# sensor_board_v0_56.net
KiCad netlist of a schematic drawn in EAGLE
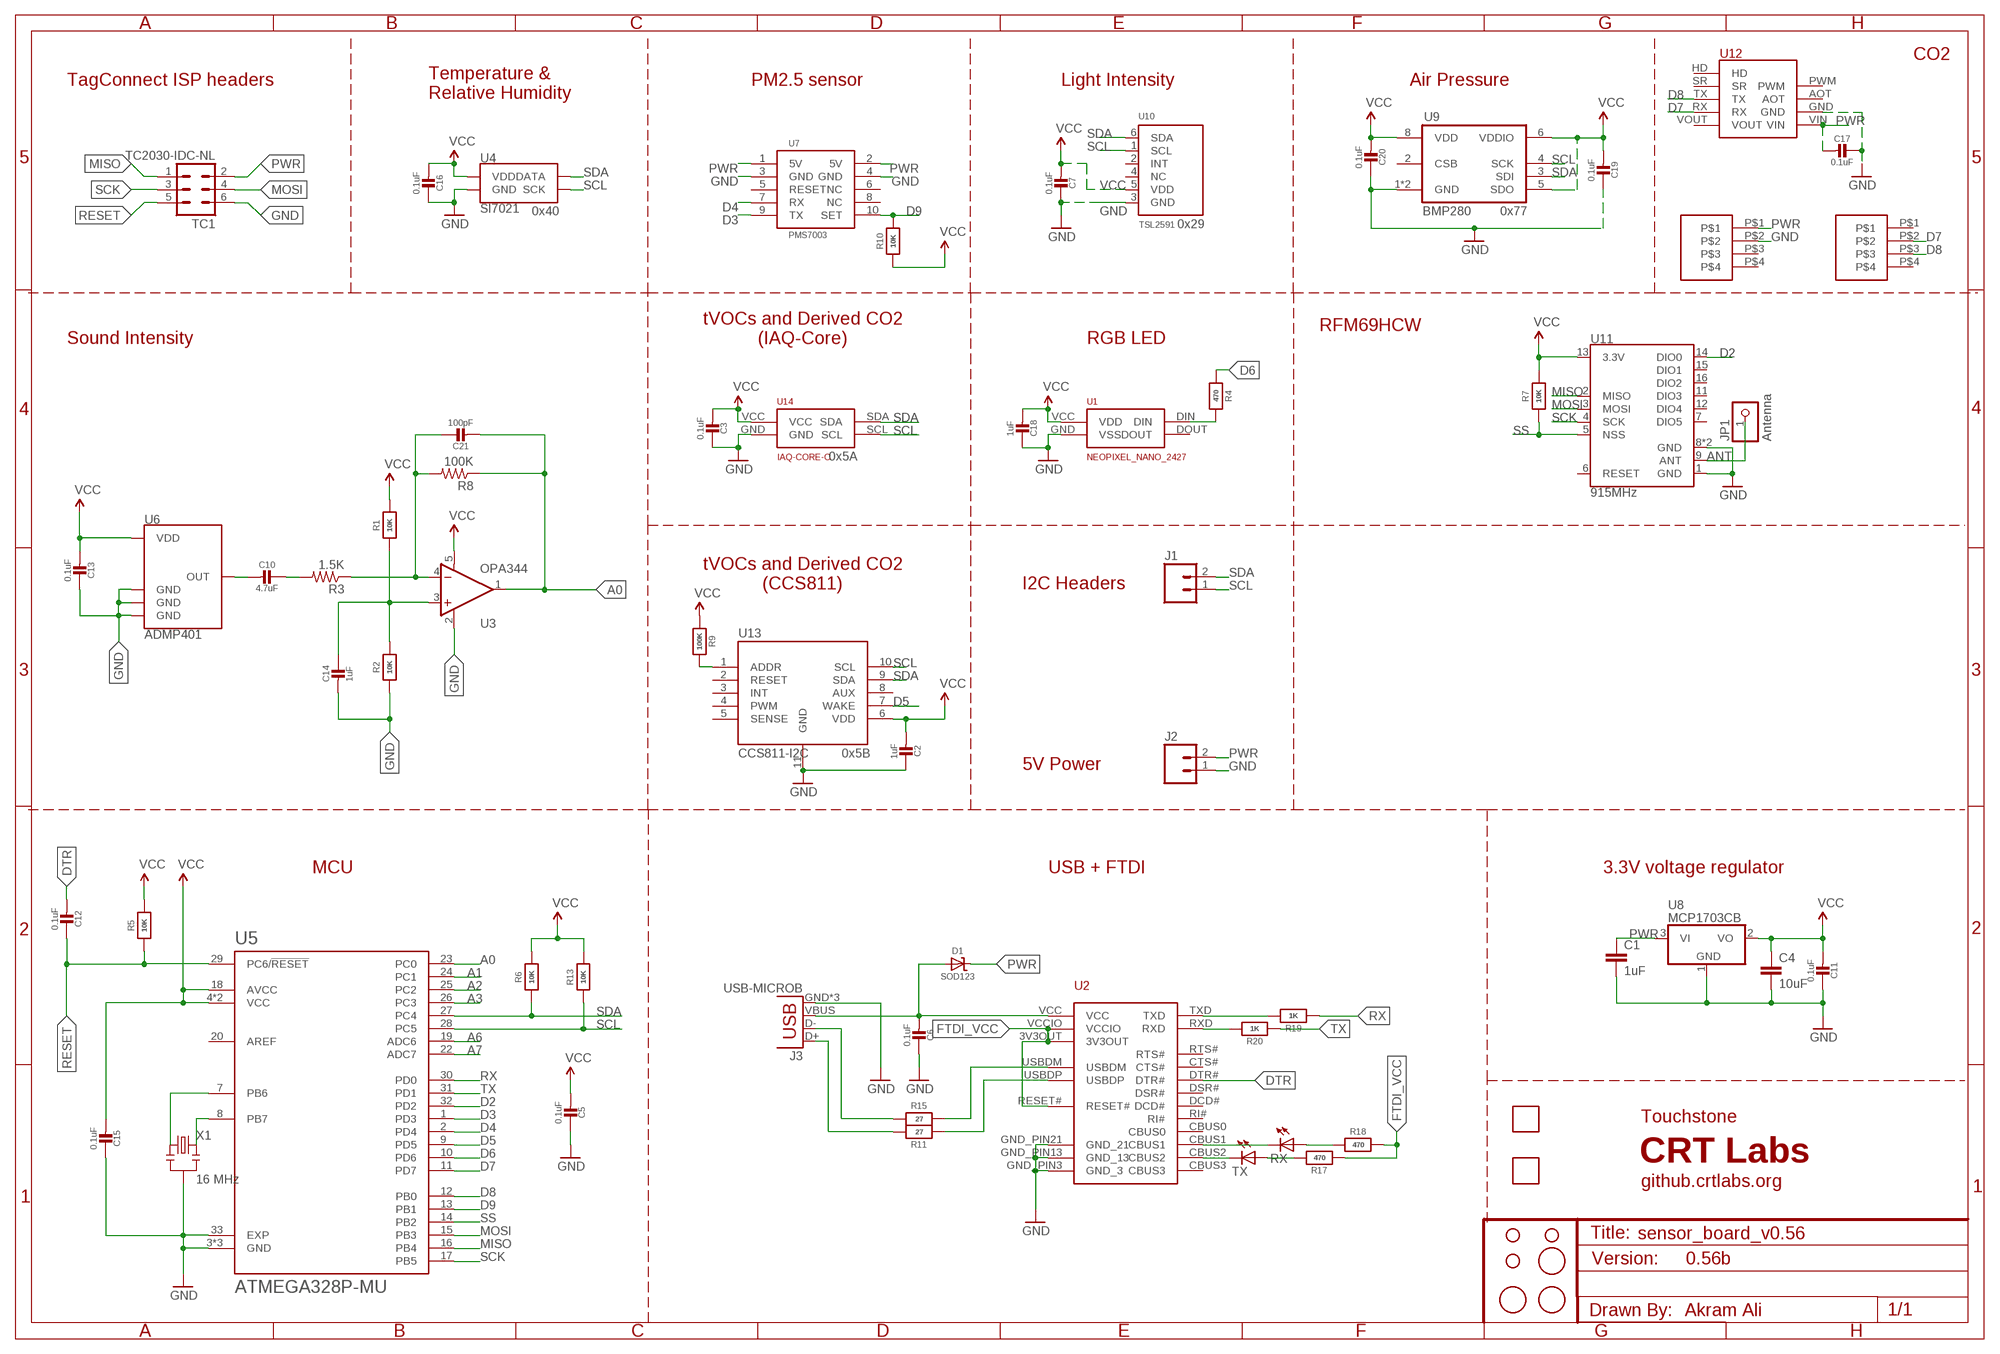
[diagram p0: schematic, sheet 1]

(export (version "E")
  (design (tool "Eeschema 10.0.6"))
  (components
    (comp (ref "C1")
      (value "1uF")
      (footprint "eagle-import:0805")
      (fields (field (name "MPN") "CC0805ZRY5V8BB105"))
      (libsource (lib "eagle-import") (part "CAP0805"))
    )
    (comp (ref "C2")
      (value "1uF")
      (footprint "eagle-import:MICROBUILDER__0402MP")
      (libsource (lib "eagle-import") (part "MICROBUILDER_CAP_CERAMIC_0402MP"))
    )
    (comp (ref "C3")
      (value "0.1uF")
      (footprint "eagle-import:MICROBUILDER__0402MP")
      (libsource (lib "eagle-import") (part "MICROBUILDER_CAP_CERAMIC_0402MP"))
    )
    (comp (ref "C4")
      (value "10uF")
      (footprint "eagle-import:0805")
      (fields (field (name "MPN") "CC0805KKX5R6BB106"))
      (libsource (lib "eagle-import") (part "CAP0805"))
    )
    (comp (ref "C5")
      (value "0.1uF")
      (footprint "eagle-import:MICROBUILDER__0402MP")
      (libsource (lib "eagle-import") (part "MICROBUILDER_CAP_CERAMIC_0402MP"))
    )
    (comp (ref "C6")
      (value "0.1uF")
      (footprint "eagle-import:MICROBUILDER__0402MP")
      (libsource (lib "eagle-import") (part "MICROBUILDER_CAP_CERAMIC_0402MP"))
    )
    (comp (ref "C7")
      (value "0.1uF")
      (footprint "eagle-import:MICROBUILDER__0402MP")
      (libsource (lib "eagle-import") (part "MICROBUILDER_CAP_CERAMIC_0402MP"))
    )
    (comp (ref "C10")
      (value "4.7uF")
      (footprint "eagle-import:MICROBUILDER__0402MP")
      (libsource (lib "eagle-import") (part "MICROBUILDER_CAP_CERAMIC_0402MP"))
    )
    (comp (ref "C11")
      (value "0.1uF")
      (footprint "eagle-import:MICROBUILDER__0402MP")
      (libsource (lib "eagle-import") (part "MICROBUILDER_CAP_CERAMIC_0402MP"))
    )
    (comp (ref "C12")
      (value "0.1uF")
      (footprint "eagle-import:MICROBUILDER__0402MP")
      (libsource (lib "eagle-import") (part "MICROBUILDER_CAP_CERAMIC_0402MP"))
    )
    (comp (ref "C13")
      (value "0.1uF")
      (footprint "eagle-import:MICROBUILDER__0402MP")
      (libsource (lib "eagle-import") (part "MICROBUILDER_CAP_CERAMIC_0402MP"))
    )
    (comp (ref "C14")
      (value "1uF")
      (footprint "eagle-import:MICROBUILDER__0402MP")
      (libsource (lib "eagle-import") (part "MICROBUILDER_CAP_CERAMIC_0402MP"))
    )
    (comp (ref "C15")
      (value "0.1uF")
      (footprint "eagle-import:MICROBUILDER__0402MP")
      (libsource (lib "eagle-import") (part "MICROBUILDER_CAP_CERAMIC_0402MP"))
    )
    (comp (ref "C16")
      (value "0.1uF")
      (footprint "eagle-import:MICROBUILDER__0402MP")
      (libsource (lib "eagle-import") (part "MICROBUILDER_CAP_CERAMIC_0402MP"))
    )
    (comp (ref "C17")
      (value "0.1uF")
      (footprint "eagle-import:MICROBUILDER__0402MP")
      (libsource (lib "eagle-import") (part "MICROBUILDER_CAP_CERAMIC_0402MP"))
    )
    (comp (ref "C18")
      (value "1uF")
      (footprint "eagle-import:MICROBUILDER__0402MP")
      (libsource (lib "eagle-import") (part "MICROBUILDER_CAP_CERAMIC_0402MP"))
    )
    (comp (ref "C19")
      (value "0.1uF")
      (footprint "eagle-import:MICROBUILDER__0402MP")
      (libsource (lib "eagle-import") (part "MICROBUILDER_CAP_CERAMIC_0402MP"))
    )
    (comp (ref "C20")
      (value "0.1uF")
      (footprint "eagle-import:MICROBUILDER__0402MP")
      (libsource (lib "eagle-import") (part "MICROBUILDER_CAP_CERAMIC_0402MP"))
    )
    (comp (ref "C21")
      (value "100pF")
      (footprint "eagle-import:MICROBUILDER__0402MP")
      (libsource (lib "eagle-import") (part "MICROBUILDER_CAP_CERAMIC_0402MP"))
    )
    (comp (ref "D1")
      (value "SOD123")
      (footprint "eagle-import:MICROBUILDER_SOD-123")
      (libsource (lib "eagle-import") (part "MICROBUILDER_DIODE-SCHOTTKYSOD-123"))
    )
    (comp (ref "H1")
      (value "STAND-OFF")
      (footprint "eagle-import:STAND-OFF")
      (libsource (lib "eagle-import") (part "STAND-OFF"))
    )
    (comp (ref "H2")
      (value "STAND-OFF")
      (footprint "eagle-import:STAND-OFF")
      (libsource (lib "eagle-import") (part "STAND-OFF"))
    )
    (comp (ref "H3")
      (value "STAND-OFF")
      (footprint "eagle-import:STAND-OFF")
      (libsource (lib "eagle-import") (part "STAND-OFF"))
    )
    (comp (ref "J1")
      (value "M02PTH")
      (footprint "eagle-import:1X02")
      (libsource (lib "eagle-import") (part "M02PTH"))
    )
    (comp (ref "J2")
      (value "M02PTH")
      (footprint "eagle-import:1X02")
      (libsource (lib "eagle-import") (part "M02PTH"))
    )
    (comp (ref "J3")
      (value "USB-MICROB")
      (footprint "eagle-import:USB-MICROB")
      (fields (field (name "MPN") "47346-0001"))
      (libsource (lib "eagle-import") (part "USB-MICROB"))
    )
    (comp (ref "JP1")
      (value "Antenna")
      (footprint "eagle-import:1X01-CLEANBIG")
      (libsource (lib "eagle-import") (part "PINHD-1X1CB"))
    )
    (comp (ref "R1")
      (value "10K")
      (footprint "eagle-import:MICROBUILDER__0402MP")
      (libsource (lib "eagle-import") (part "MICROBUILDER_RESISTOR_0402MP"))
    )
    (comp (ref "R2")
      (value "10K")
      (footprint "eagle-import:MICROBUILDER__0402MP")
      (libsource (lib "eagle-import") (part "MICROBUILDER_RESISTOR_0402MP"))
    )
    (comp (ref "R3")
      (value "1.5K")
      (footprint "eagle-import:0805")
      (fields (field (name "MPN") "RC0805FR-071K5L "))
      (libsource (lib "eagle-import") (part "RESISTOR0805-RES"))
    )
    (comp (ref "R4")
      (value "470")
      (footprint "eagle-import:MICROBUILDER__0402MP")
      (libsource (lib "eagle-import") (part "MICROBUILDER_RESISTOR_0402MP"))
    )
    (comp (ref "R5")
      (value "10K")
      (footprint "eagle-import:MICROBUILDER__0402MP")
      (libsource (lib "eagle-import") (part "MICROBUILDER_RESISTOR_0402MP"))
    )
    (comp (ref "R6")
      (value "10K")
      (footprint "eagle-import:MICROBUILDER__0402MP")
      (libsource (lib "eagle-import") (part "MICROBUILDER_RESISTOR_0402MP"))
    )
    (comp (ref "R7")
      (value "10K")
      (footprint "eagle-import:MICROBUILDER__0402MP")
      (libsource (lib "eagle-import") (part "MICROBUILDER_RESISTOR_0402MP"))
    )
    (comp (ref "R8")
      (value "100K")
      (footprint "eagle-import:0805")
      (fields (field (name "MPN") "RC0805FR-07100KL "))
      (libsource (lib "eagle-import") (part "RESISTOR0805-RES"))
    )
    (comp (ref "R9")
      (value "100K")
      (footprint "eagle-import:MICROBUILDER__0402MP")
      (libsource (lib "eagle-import") (part "MICROBUILDER_RESISTOR_0402MP"))
    )
    (comp (ref "R10")
      (value "10K")
      (footprint "eagle-import:MICROBUILDER__0402MP")
      (libsource (lib "eagle-import") (part "MICROBUILDER_RESISTOR_0402MP"))
    )
    (comp (ref "R11")
      (value "27")
      (footprint "eagle-import:MICROBUILDER__0402MP")
      (libsource (lib "eagle-import") (part "MICROBUILDER_RESISTOR_0402MP"))
    )
    (comp (ref "R13")
      (value "10K")
      (footprint "eagle-import:MICROBUILDER__0402MP")
      (libsource (lib "eagle-import") (part "MICROBUILDER_RESISTOR_0402MP"))
    )
    (comp (ref "R15")
      (value "27")
      (footprint "eagle-import:MICROBUILDER__0402MP")
      (libsource (lib "eagle-import") (part "MICROBUILDER_RESISTOR_0402MP"))
    )
    (comp (ref "R17")
      (value "470")
      (footprint "eagle-import:MICROBUILDER__0402MP")
      (libsource (lib "eagle-import") (part "MICROBUILDER_RESISTOR_0402MP"))
    )
    (comp (ref "R18")
      (value "470")
      (footprint "eagle-import:MICROBUILDER__0402MP")
      (libsource (lib "eagle-import") (part "MICROBUILDER_RESISTOR_0402MP"))
    )
    (comp (ref "R19")
      (value "1K")
      (footprint "eagle-import:MICROBUILDER__0402MP")
      (libsource (lib "eagle-import") (part "MICROBUILDER_RESISTOR_0402MP"))
    )
    (comp (ref "R20")
      (value "1K")
      (footprint "eagle-import:MICROBUILDER__0402MP")
      (libsource (lib "eagle-import") (part "MICROBUILDER_RESISTOR_0402MP"))
    )
    (comp (ref "RX")
      (value "LEDCHIPLED_0805")
      (footprint "eagle-import:CHIPLED_0805")
      (fields (field (name "MPN") "LG R971-KN-1"))
      (libsource (lib "eagle-import") (part "LEDCHIPLED_0805"))
    )
    (comp (ref "TC1")
      (value "TC2030-IDC-NL")
      (footprint "eagle-import:TC2030-IDC-NL")
      (libsource (lib "eagle-import") (part "TC2030-IDC-NL"))
    )
    (comp (ref "TX")
      (value "LEDCHIPLED_0805")
      (footprint "eagle-import:CHIPLED_0805")
      (fields (field (name "MPN") "LG R971-KN-1"))
      (libsource (lib "eagle-import") (part "LEDCHIPLED_0805"))
    )
    (comp (ref "U$1")
      (value "FIDUCIAL")
      (footprint "eagle-import:FIDUCIAL_1MM")
      (libsource (lib "eagle-import") (part "FIDUCIAL"))
    )
    (comp (ref "U$2")
      (value "FIDUCIAL")
      (footprint "eagle-import:FIDUCIAL_1MM")
      (libsource (lib "eagle-import") (part "FIDUCIAL"))
    )
    (comp (ref "U$3")
      (value "FIDUCIAL")
      (footprint "eagle-import:FIDUCIAL_1MM")
      (libsource (lib "eagle-import") (part "FIDUCIAL"))
    )
    (comp (ref "U$4")
      (value "0878980426")
      (footprint "eagle-import:CONN_4POS_VERT_2.54_SMD")
      (libsource (lib "eagle-import") (part "0878980426"))
    )
    (comp (ref "U$5")
      (value "0878980426")
      (footprint "eagle-import:CONN_4POS_VERT_2.54_SMD")
      (libsource (lib "eagle-import") (part "0878980426"))
    )
    (comp (ref "U1")
      (value "NEOPIXEL_NANO_2427")
      (footprint "eagle-import:SK6805-2427")
      (libsource (lib "eagle-import") (part "NEOPIXEL_NANO_2427"))
    )
    (comp (ref "U2")
      (value "FT231XQ-R")
      (footprint "eagle-import:FTDI_FT231XQ-R_PACKAGE")
      (libsource (lib "eagle-import") (part "FT231XQ-R"))
    )
    (comp (ref "U3")
      (value "OPA344")
      (footprint "eagle-import:SOT23-5")
      (fields (field (name "MPN") "OPA344NA/3K"))
      (libsource (lib "eagle-import") (part "OPA344"))
    )
    (comp (ref "U4")
      (value "SI7021")
      (footprint "eagle-import:DFN-6-3X3-SI7021")
      (libsource (lib "eagle-import") (part "SI7021"))
    )
    (comp (ref "U5")
      (value "ATMEGA328P-MU")
      (footprint "eagle-import:QFN50P500X500X100-33N")
      (fields (field (name "MF") "Atmel"))
      (libsource (lib "eagle-import") (part "ATMEGA328P-MU"))
    )
    (comp (ref "U6")
      (value "ADMP401")
      (footprint "eagle-import:ADMP401")
      (fields (field (name "MPN") "INMP401ACEZ-R7"))
      (libsource (lib "eagle-import") (part "ADMP401"))
    )
    (comp (ref "U7")
      (value "PMS7003")
      (footprint "eagle-import:PMS7003_RECEPTACLE_1.27MM_2X5")
      (libsource (lib "eagle-import") (part "PMS7003"))
    )
    (comp (ref "U8")
      (value "MCP1703CB")
      (footprint "eagle-import:SOT23")
      (fields (field (name "MPN") "MCP1703T-2502E/CB"))
      (libsource (lib "eagle-import") (part "MCP1703CB"))
    )
    (comp (ref "U9")
      (value "BMP280")
      (footprint "eagle-import:BMP280")
      (libsource (lib "eagle-import") (part "BMP280"))
    )
    (comp (ref "U10")
      (value "TSL2591")
      (footprint "eagle-import:DFN6_TAOS")
      (fields (field (name "MPN") "TSL25911FN "))
      (libsource (lib "eagle-import") (part "LIGHT_TSL2591"))
    )
    (comp (ref "U11")
      (value "915MHz")
      (footprint "eagle-import:RFM69HCW-XXXS2")
      (libsource (lib "eagle-import") (part "RFM69HCW-915"))
    )
    (comp (ref "U12")
      (value "MH-Z19")
      (footprint "eagle-import:MH-Z19")
      (fields (field (name "MPN") "MH-z19"))
      (libsource (lib "eagle-import") (part "MH-Z19"))
    )
    (comp (ref "U13")
      (value "CCS811-I2C")
      (footprint "eagle-import:LGA")
      (libsource (lib "eagle-import") (part "CCS811-I2C"))
    )
    (comp (ref "U14")
      (value "IAQ-CORE-C")
      (footprint "eagle-import:IAQ-CORE-C")
      (libsource (lib "eagle-import") (part "IAQ-CORE-C"))
    )
    (comp (ref "U15")
      (value "VLP-450-F")
      (footprint "eagle-import:VLP-450-F")
      (libsource (lib "eagle-import") (part "VLP-450-F"))
    )
    (comp (ref "U16")
      (value "VLP-450-F")
      (footprint "eagle-import:VLP-450-F")
      (libsource (lib "eagle-import") (part "VLP-450-F"))
    )
    (comp (ref "X1")
      (value "16 MHz")
      (footprint "eagle-import:RESONATOR-SMD")
      (libsource (lib "eagle-import") (part "RESONATORSMD"))
    )
  )
  (nets
    (net (code "1") (name "/A1") (class "Default")
      (node (ref "U5") (pin "24") (pinfunction "PC1_24") (pintype "bidirectional"))
    )
    (net (code "2") (name "/A2") (class "Default")
      (node (ref "U5") (pin "25") (pinfunction "PC2_25") (pintype "bidirectional"))
    )
    (net (code "3") (name "/A3") (class "Default")
      (node (ref "U5") (pin "26") (pinfunction "PC3_26") (pintype "bidirectional"))
    )
    (net (code "4") (name "/A6") (class "Default")
      (node (ref "U5") (pin "19") (pinfunction "ADC6_19") (pintype "bidirectional"))
    )
    (net (code "5") (name "/A7") (class "Default")
      (node (ref "U5") (pin "22") (pinfunction "ADC7_22") (pintype "bidirectional"))
    )
    (net (code "6") (name "/ANT") (class "Default")
      (node (ref "JP1") (pin "1") (pinfunction "1_1") (pintype "passive"))
      (node (ref "U11") (pin "9") (pinfunction "ANT_9") (pintype "passive"))
    )
    (net (code "7") (name "/D2") (class "Default")
      (node (ref "U11") (pin "14") (pinfunction "DIO0_14") (pintype "bidirectional"))
      (node (ref "U5") (pin "32") (pinfunction "PD2_32") (pintype "bidirectional"))
    )
    (net (code "8") (name "/D3") (class "Default")
      (node (ref "U5") (pin "1") (pinfunction "PD3_1") (pintype "bidirectional"))
      (node (ref "U7") (pin "9") (pinfunction "TX_9") (pintype "bidirectional"))
    )
    (net (code "9") (name "/D4") (class "Default")
      (node (ref "U5") (pin "2") (pinfunction "PD4_2") (pintype "bidirectional"))
      (node (ref "U7") (pin "7") (pinfunction "RX_7") (pintype "bidirectional"))
    )
    (net (code "10") (name "/D5") (class "Default")
      (node (ref "U13") (pin "7") (pinfunction "WAKE_7") (pintype "bidirectional"))
      (node (ref "U5") (pin "9") (pinfunction "PD5_9") (pintype "bidirectional"))
    )
    (net (code "11") (name "/D7") (class "Default")
      (node (ref "U$5") (pin "P$2") (pinfunction "P$2_P$2") (pintype "bidirectional"))
      (node (ref "U12") (pin "RX") (pinfunction "RX_RX") (pintype "bidirectional"))
      (node (ref "U5") (pin "11") (pinfunction "PD7_11") (pintype "bidirectional"))
    )
    (net (code "12") (name "/D8") (class "Default")
      (node (ref "U$5") (pin "P$3") (pinfunction "P$3_P$3") (pintype "bidirectional"))
      (node (ref "U12") (pin "TX") (pinfunction "TX_TX") (pintype "bidirectional"))
      (node (ref "U5") (pin "12") (pinfunction "PB0_12") (pintype "bidirectional"))
    )
    (net (code "13") (name "/D9") (class "Default")
      (node (ref "R10") (pin "2") (pinfunction "2_2") (pintype "passive"))
      (node (ref "U5") (pin "13") (pinfunction "PB1_13") (pintype "bidirectional"))
      (node (ref "U7") (pin "10") (pinfunction "SET_10") (pintype "bidirectional"))
    )
    (net (code "14") (name "/SCL") (class "Default")
      (node (ref "J1") (pin "1") (pinfunction "1_1") (pintype "passive"))
      (node (ref "R13") (pin "1") (pinfunction "1_1") (pintype "passive"))
      (node (ref "U10") (pin "1") (pinfunction "SCL_1") (pintype "bidirectional"))
      (node (ref "U13") (pin "10") (pinfunction "SCL_10") (pintype "bidirectional"))
      (node (ref "U14") (pin "SCL") (pinfunction "SCL_SCL") (pintype "bidirectional"))
      (node (ref "U4") (pin "SCK") (pinfunction "SCK_SCK") (pintype "input"))
      (node (ref "U5") (pin "28") (pinfunction "PC5_28") (pintype "bidirectional"))
      (node (ref "U9") (pin "4") (pinfunction "SCK_4") (pintype "bidirectional"))
    )
    (net (code "15") (name "/SDA") (class "Default")
      (node (ref "J1") (pin "2") (pinfunction "2_2") (pintype "passive"))
      (node (ref "R6") (pin "1") (pinfunction "1_1") (pintype "passive"))
      (node (ref "U10") (pin "6") (pinfunction "SDA_6") (pintype "bidirectional"))
      (node (ref "U13") (pin "9") (pinfunction "SDA_9") (pintype "bidirectional"))
      (node (ref "U14") (pin "SDA") (pinfunction "SDA_SDA") (pintype "bidirectional"))
      (node (ref "U4") (pin "DATA") (pinfunction "DATA_DATA") (pintype "bidirectional"))
      (node (ref "U5") (pin "27") (pinfunction "PC4_27") (pintype "bidirectional"))
      (node (ref "U9") (pin "3") (pinfunction "SDI_3") (pintype "bidirectional"))
    )
    (net (code "16") (name "/SS") (class "Default")
      (node (ref "R7") (pin "1") (pinfunction "1_1") (pintype "passive"))
      (node (ref "U11") (pin "5") (pinfunction "NSS_5") (pintype "input"))
      (node (ref "U5") (pin "14") (pinfunction "PB2_14") (pintype "bidirectional"))
    )
    (net (code "17") (name "A0") (class "Default")
      (node (ref "C21") (pin "2") (pinfunction "2_2") (pintype "passive"))
      (node (ref "R8") (pin "1") (pinfunction "1_1") (pintype "passive"))
      (node (ref "U3") (pin "1") (pinfunction "OUT_1") (pintype "output"))
      (node (ref "U5") (pin "23") (pinfunction "PC0_23") (pintype "bidirectional"))
    )
    (net (code "18") (name "D6") (class "Default")
      (node (ref "R4") (pin "1") (pinfunction "1_1") (pintype "passive"))
      (node (ref "U5") (pin "10") (pinfunction "PD6_10") (pintype "bidirectional"))
    )
    (net (code "19") (name "DTR") (class "Default")
      (node (ref "C12") (pin "2") (pinfunction "2_2") (pintype "passive"))
      (node (ref "U2") (pin "DTR#") (pinfunction "DTR#_DTR#") (pintype "bidirectional"))
    )
    (net (code "20") (name "FTDI_VCC") (class "Default")
      (node (ref "R17") (pin "1") (pinfunction "1_1") (pintype "passive"))
      (node (ref "R18") (pin "2") (pinfunction "2_2") (pintype "passive"))
      (node (ref "U2") (pin "3V3OUT") (pinfunction "3V3OUT_3V3OUT") (pintype "bidirectional"))
      (node (ref "U2") (pin "RESET#") (pinfunction "RESET#_RESET#") (pintype "bidirectional"))
      (node (ref "U2") (pin "VCCIO") (pinfunction "VCCIO_VCCIO") (pintype "bidirectional"))
    )
    (net (code "21") (name "GND") (class "Default")
      (node (ref "C1") (pin "2") (pinfunction "2_2") (pintype "passive"))
      (node (ref "C11") (pin "1") (pinfunction "1_1") (pintype "passive"))
      (node (ref "C13") (pin "1") (pinfunction "1_1") (pintype "passive"))
      (node (ref "C14") (pin "2") (pinfunction "2_2") (pintype "passive"))
      (node (ref "C15") (pin "1") (pinfunction "1_1") (pintype "passive"))
      (node (ref "C16") (pin "1") (pinfunction "1_1") (pintype "passive"))
      (node (ref "C17") (pin "1") (pinfunction "1_1") (pintype "passive"))
      (node (ref "C18") (pin "1") (pinfunction "1_1") (pintype "passive"))
      (node (ref "C19") (pin "1") (pinfunction "1_1") (pintype "passive"))
      (node (ref "C2") (pin "1") (pinfunction "1_1") (pintype "passive"))
      (node (ref "C20") (pin "1") (pinfunction "1_1") (pintype "passive"))
      (node (ref "C3") (pin "1") (pinfunction "1_1") (pintype "passive"))
      (node (ref "C4") (pin "2") (pinfunction "2_2") (pintype "passive"))
      (node (ref "C5") (pin "1") (pinfunction "1_1") (pintype "passive"))
      (node (ref "C6") (pin "1") (pinfunction "1_1") (pintype "passive"))
      (node (ref "C7") (pin "1") (pinfunction "1_1") (pintype "passive"))
      (node (ref "J2") (pin "1") (pinfunction "1_1") (pintype "passive"))
      (node (ref "J3") (pin "GND") (pinfunction "GND_GND") (pintype "bidirectional"))
      (node (ref "J3") (pin "MT1") (pinfunction "GND_MT1") (pintype "bidirectional"))
      (node (ref "J3") (pin "MT2") (pinfunction "GND_MT2") (pintype "bidirectional"))
      (node (ref "R2") (pin "1") (pinfunction "1_1") (pintype "passive"))
      (node (ref "TC1") (pin "6") (pinfunction "6_6") (pintype "passive"))
      (node (ref "U$4") (pin "P$2") (pinfunction "P$2_P$2") (pintype "bidirectional"))
      (node (ref "U1") (pin "GND") (pinfunction "VSS_GND") (pintype "bidirectional"))
      (node (ref "U10") (pin "3") (pinfunction "GND_3") (pintype "power_in"))
      (node (ref "U11") (pin "1") (pinfunction "GND_1") (pintype "power_in"))
      (node (ref "U11") (pin "10") (pinfunction "GND_10") (pintype "power_in"))
      (node (ref "U11") (pin "8") (pinfunction "GND_8") (pintype "power_in"))
      (node (ref "U12") (pin "GND") (pinfunction "GND_GND") (pintype "bidirectional"))
      (node (ref "U13") (pin "11") (pinfunction "GND_11") (pintype "bidirectional"))
      (node (ref "U14") (pin "GND") (pinfunction "GND_GND") (pintype "bidirectional"))
      (node (ref "U2") (pin "GND_PIN13") (pinfunction "GND_13_GND_PIN13") (pintype "bidirectional"))
      (node (ref "U2") (pin "GND_PIN21") (pinfunction "GND_21_GND_PIN21") (pintype "bidirectional"))
      (node (ref "U2") (pin "GND_PIN3") (pinfunction "GND_3_GND_PIN3") (pintype "bidirectional"))
      (node (ref "U3") (pin "2") (pinfunction "V-_2") (pintype "power_in"))
      (node (ref "U4") (pin "GND") (pinfunction "GND_GND") (pintype "power_in"))
      (node (ref "U5") (pin "21") (pinfunction "GND_21") (pintype "power_in"))
      (node (ref "U5") (pin "3") (pinfunction "GND_3") (pintype "power_in"))
      (node (ref "U5") (pin "33") (pinfunction "EXP_33") (pintype "power_in"))
      (node (ref "U5") (pin "5") (pinfunction "GND_5") (pintype "power_in"))
      (node (ref "U6") (pin "2") (pinfunction "GND_2") (pintype "bidirectional"))
      (node (ref "U6") (pin "4") (pinfunction "GND_4") (pintype "bidirectional"))
      (node (ref "U6") (pin "6") (pinfunction "GND_6") (pintype "bidirectional"))
      (node (ref "U7") (pin "3") (pinfunction "GND_3") (pintype "bidirectional"))
      (node (ref "U7") (pin "4") (pinfunction "GND_4") (pintype "bidirectional"))
      (node (ref "U8") (pin "1") (pinfunction "GND_1") (pintype "passive"))
      (node (ref "U9") (pin "1") (pinfunction "GND_1") (pintype "power_in"))
      (node (ref "U9") (pin "7") (pinfunction "GND_7") (pintype "power_in"))
      (node (ref "X1") (pin "2") (pinfunction "2_2") (pintype "passive"))
    )
    (net (code "22") (name "MISO") (class "Default")
      (node (ref "TC1") (pin "1") (pinfunction "1_1") (pintype "passive"))
      (node (ref "U11") (pin "2") (pinfunction "MISO_2") (pintype "bidirectional"))
      (node (ref "U5") (pin "16") (pinfunction "PB4_16") (pintype "bidirectional"))
    )
    (net (code "23") (name "MOSI") (class "Default")
      (node (ref "TC1") (pin "4") (pinfunction "4_4") (pintype "passive"))
      (node (ref "U11") (pin "3") (pinfunction "MOSI_3") (pintype "input"))
      (node (ref "U5") (pin "15") (pinfunction "PB3_15") (pintype "bidirectional"))
    )
    (net (code "24") (name "Net-(C6-Pad2)") (class "Default")
      (node (ref "C6") (pin "2") (pinfunction "2_2") (pintype "passive"))
      (node (ref "D1") (pin "A") (pinfunction "A_A") (pintype "passive"))
      (node (ref "J3") (pin "VBUS") (pinfunction "VBUS_VBUS") (pintype "bidirectional"))
      (node (ref "U2") (pin "VCC") (pinfunction "VCC_VCC") (pintype "bidirectional"))
    )
    (net (code "25") (name "Net-(C10-Pad1)") (class "Default")
      (node (ref "C10") (pin "1") (pinfunction "1_1") (pintype "passive"))
      (node (ref "R3") (pin "2") (pinfunction "2_2") (pintype "passive"))
    )
    (net (code "26") (name "Net-(J3-PadD+)") (class "Default")
      (node (ref "J3") (pin "D+") (pinfunction "D+_D+") (pintype "bidirectional"))
      (node (ref "R11") (pin "2") (pinfunction "2_2") (pintype "passive"))
    )
    (net (code "27") (name "Net-(J3-PadD-)") (class "Default")
      (node (ref "J3") (pin "D-") (pinfunction "D-_D-") (pintype "bidirectional"))
      (node (ref "R15") (pin "1") (pinfunction "1_1") (pintype "passive"))
    )
    (net (code "28") (name "Net-(R4-Pad2)") (class "Default")
      (node (ref "R4") (pin "2") (pinfunction "2_2") (pintype "passive"))
      (node (ref "U1") (pin "DIN") (pinfunction "DIN_DIN") (pintype "bidirectional"))
    )
    (net (code "29") (name "Net-(R11-Pad1)") (class "Default")
      (node (ref "R11") (pin "1") (pinfunction "1_1") (pintype "passive"))
      (node (ref "U2") (pin "USBDP") (pinfunction "USBDP_USBDP") (pintype "bidirectional"))
    )
    (net (code "30") (name "Net-(R15-Pad2)") (class "Default")
      (node (ref "R15") (pin "2") (pinfunction "2_2") (pintype "passive"))
      (node (ref "U2") (pin "USBDM") (pinfunction "USBDM_USBDM") (pintype "bidirectional"))
    )
    (net (code "31") (name "Net-(R17-Pad2)") (class "Default")
      (node (ref "R17") (pin "2") (pinfunction "2_2") (pintype "passive"))
      (node (ref "TX") (pin "A") (pinfunction "A_A") (pintype "passive"))
    )
    (net (code "32") (name "Net-(R18-Pad1)") (class "Default")
      (node (ref "R18") (pin "1") (pinfunction "1_1") (pintype "passive"))
      (node (ref "RX") (pin "A") (pinfunction "A_A") (pintype "passive"))
    )
    (net (code "33") (name "Net-(R19-Pad2)") (class "Default")
      (node (ref "R19") (pin "2") (pinfunction "2_2") (pintype "passive"))
      (node (ref "U2") (pin "TXD") (pinfunction "TXD_TXD") (pintype "bidirectional"))
    )
    (net (code "34") (name "Net-(R20-Pad2)") (class "Default")
      (node (ref "R20") (pin "2") (pinfunction "2_2") (pintype "passive"))
      (node (ref "U2") (pin "RXD") (pinfunction "RXD_RXD") (pintype "bidirectional"))
    )
    (net (code "35") (name "Net-(RX-PadC)") (class "Default")
      (node (ref "RX") (pin "C") (pinfunction "C_C") (pintype "passive"))
      (node (ref "U2") (pin "CBUS1") (pinfunction "CBUS1_CBUS1") (pintype "bidirectional"))
    )
    (net (code "36") (name "Net-(TX-PadC)") (class "Default")
      (node (ref "TX") (pin "C") (pinfunction "C_C") (pintype "passive"))
      (node (ref "U2") (pin "CBUS2") (pinfunction "CBUS2_CBUS2") (pintype "bidirectional"))
    )
    (net (code "37") (name "Net-(U3-+IN)") (class "Default")
      (node (ref "C14") (pin "1") (pinfunction "1_1") (pintype "passive"))
      (node (ref "R1") (pin "1") (pinfunction "1_1") (pintype "passive"))
      (node (ref "R2") (pin "2") (pinfunction "2_2") (pintype "passive"))
      (node (ref "U3") (pin "3") (pinfunction "+IN_3") (pintype "input"))
    )
    (net (code "38") (name "Net-(U3--IN)") (class "Default")
      (node (ref "C21") (pin "1") (pinfunction "1_1") (pintype "passive"))
      (node (ref "R3") (pin "1") (pinfunction "1_1") (pintype "passive"))
      (node (ref "R8") (pin "2") (pinfunction "2_2") (pintype "passive"))
      (node (ref "U3") (pin "4") (pinfunction "-IN_4") (pintype "input"))
    )
    (net (code "39") (name "Net-(U5-PB6)") (class "Default")
      (node (ref "U5") (pin "7") (pinfunction "PB6_7") (pintype "bidirectional"))
      (node (ref "X1") (pin "1") (pinfunction "1_1") (pintype "passive"))
    )
    (net (code "40") (name "Net-(U5-PB7)") (class "Default")
      (node (ref "U5") (pin "8") (pinfunction "PB7_8") (pintype "bidirectional"))
      (node (ref "X1") (pin "3") (pinfunction "3_3") (pintype "passive"))
    )
    (net (code "41") (name "Net-(U6-OUT)") (class "Default")
      (node (ref "C10") (pin "2") (pinfunction "2_2") (pintype "passive"))
      (node (ref "U6") (pin "1") (pinfunction "OUT_1") (pintype "bidirectional"))
    )
    (net (code "42") (name "Net-(U13-ADDR)") (class "Default")
      (node (ref "R9") (pin "2") (pinfunction "2_2") (pintype "passive"))
      (node (ref "U13") (pin "1") (pinfunction "ADDR_1") (pintype "bidirectional"))
    )
    (net (code "43") (name "PWR") (class "Default")
      (node (ref "C1") (pin "1") (pinfunction "1_1") (pintype "passive"))
      (node (ref "C17") (pin "2") (pinfunction "2_2") (pintype "passive"))
      (node (ref "D1") (pin "C") (pinfunction "C_C") (pintype "passive"))
      (node (ref "J2") (pin "2") (pinfunction "2_2") (pintype "passive"))
      (node (ref "TC1") (pin "2") (pinfunction "2_2") (pintype "passive"))
      (node (ref "U$4") (pin "P$1") (pinfunction "P$1_P$1") (pintype "bidirectional"))
      (node (ref "U12") (pin "VIN") (pinfunction "VIN_VIN") (pintype "bidirectional"))
      (node (ref "U7") (pin "1") (pinfunction "5V_1") (pintype "bidirectional"))
      (node (ref "U7") (pin "2") (pinfunction "5V_2") (pintype "bidirectional"))
      (node (ref "U8") (pin "3") (pinfunction "VI_3") (pintype "input"))
    )
    (net (code "44") (name "RESET") (class "Default")
      (node (ref "C12") (pin "1") (pinfunction "1_1") (pintype "passive"))
      (node (ref "R5") (pin "1") (pinfunction "1_1") (pintype "passive"))
      (node (ref "TC1") (pin "5") (pinfunction "5_5") (pintype "passive"))
      (node (ref "U5") (pin "29") (pinfunction "PC6/~{RESET}_29") (pintype "bidirectional"))
    )
    (net (code "45") (name "RX") (class "Default")
      (node (ref "R19") (pin "1") (pinfunction "1_1") (pintype "passive"))
      (node (ref "U5") (pin "30") (pinfunction "PD0_30") (pintype "bidirectional"))
    )
    (net (code "46") (name "SCK") (class "Default")
      (node (ref "TC1") (pin "3") (pinfunction "3_3") (pintype "passive"))
      (node (ref "U11") (pin "4") (pinfunction "SCK_4") (pintype "input"))
      (node (ref "U5") (pin "17") (pinfunction "PB5_17") (pintype "bidirectional"))
    )
    (net (code "47") (name "TX") (class "Default")
      (node (ref "R20") (pin "1") (pinfunction "1_1") (pintype "passive"))
      (node (ref "U5") (pin "31") (pinfunction "PD1_31") (pintype "bidirectional"))
    )
    (net (code "48") (name "VCC") (class "Default")
      (node (ref "C11") (pin "2") (pinfunction "2_2") (pintype "passive"))
      (node (ref "C13") (pin "2") (pinfunction "2_2") (pintype "passive"))
      (node (ref "C15") (pin "2") (pinfunction "2_2") (pintype "passive"))
      (node (ref "C16") (pin "2") (pinfunction "2_2") (pintype "passive"))
      (node (ref "C18") (pin "2") (pinfunction "2_2") (pintype "passive"))
      (node (ref "C19") (pin "2") (pinfunction "2_2") (pintype "passive"))
      (node (ref "C2") (pin "2") (pinfunction "2_2") (pintype "passive"))
      (node (ref "C20") (pin "2") (pinfunction "2_2") (pintype "passive"))
      (node (ref "C3") (pin "2") (pinfunction "2_2") (pintype "passive"))
      (node (ref "C4") (pin "1") (pinfunction "1_1") (pintype "passive"))
      (node (ref "C5") (pin "2") (pinfunction "2_2") (pintype "passive"))
      (node (ref "C7") (pin "2") (pinfunction "2_2") (pintype "passive"))
      (node (ref "R1") (pin "2") (pinfunction "2_2") (pintype "passive"))
      (node (ref "R10") (pin "1") (pinfunction "1_1") (pintype "passive"))
      (node (ref "R13") (pin "2") (pinfunction "2_2") (pintype "passive"))
      (node (ref "R5") (pin "2") (pinfunction "2_2") (pintype "passive"))
      (node (ref "R6") (pin "2") (pinfunction "2_2") (pintype "passive"))
      (node (ref "R7") (pin "2") (pinfunction "2_2") (pintype "passive"))
      (node (ref "R9") (pin "1") (pinfunction "1_1") (pintype "passive"))
      (node (ref "U1") (pin "VCC") (pinfunction "VDD_VCC") (pintype "bidirectional"))
      (node (ref "U10") (pin "5") (pinfunction "VDD_5") (pintype "power_in"))
      (node (ref "U11") (pin "13") (pinfunction "3.3V_13") (pintype "power_in"))
      (node (ref "U13") (pin "6") (pinfunction "VDD_6") (pintype "bidirectional"))
      (node (ref "U14") (pin "VCC") (pinfunction "VCC_VCC") (pintype "bidirectional"))
      (node (ref "U3") (pin "5") (pinfunction "V+_5") (pintype "power_in"))
      (node (ref "U4") (pin "VDD") (pinfunction "VDD_VDD") (pintype "power_in"))
      (node (ref "U5") (pin "18") (pinfunction "AVCC_18") (pintype "power_in"))
      (node (ref "U5") (pin "4") (pinfunction "VCC_4") (pintype "power_in"))
      (node (ref "U5") (pin "6") (pinfunction "VCC_6") (pintype "power_in"))
      (node (ref "U6") (pin "5") (pinfunction "VDD_5") (pintype "bidirectional"))
      (node (ref "U8") (pin "2") (pinfunction "VO_2") (pintype "passive"))
      (node (ref "U9") (pin "5") (pinfunction "SDO_5") (pintype "input"))
      (node (ref "U9") (pin "6") (pinfunction "VDDIO_6") (pintype "power_in"))
      (node (ref "U9") (pin "8") (pinfunction "VDD_8") (pintype "power_in"))
    )
    (net (code "49") (name "unconnected-(U$4-PadP$3)") (class "Default")
      (node (ref "U$4") (pin "P$3") (pinfunction "P$3_P$3") (pintype "bidirectional"))
    )
    (net (code "50") (name "unconnected-(U$4-PadP$4)") (class "Default")
      (node (ref "U$4") (pin "P$4") (pinfunction "P$4_P$4") (pintype "bidirectional"))
    )
    (net (code "51") (name "unconnected-(U$5-PadP$1)") (class "Default")
      (node (ref "U$5") (pin "P$1") (pinfunction "P$1_P$1") (pintype "bidirectional"))
    )
    (net (code "52") (name "unconnected-(U$5-PadP$4)") (class "Default")
      (node (ref "U$5") (pin "P$4") (pinfunction "P$4_P$4") (pintype "bidirectional"))
    )
    (net (code "53") (name "unconnected-(U1-PadDOUT)") (class "Default")
      (node (ref "U1") (pin "DOUT") (pinfunction "DOUT_DOUT") (pintype "bidirectional"))
    )
    (net (code "54") (name "unconnected-(U2-PadCBUS0)") (class "Default")
      (node (ref "U2") (pin "CBUS0") (pinfunction "CBUS0_CBUS0") (pintype "bidirectional"))
    )
    (net (code "55") (name "unconnected-(U2-PadCBUS3)") (class "Default")
      (node (ref "U2") (pin "CBUS3") (pinfunction "CBUS3_CBUS3") (pintype "bidirectional"))
    )
    (net (code "56") (name "unconnected-(U2-PadCTS#)") (class "Default")
      (node (ref "U2") (pin "CTS#") (pinfunction "CTS#_CTS#") (pintype "bidirectional"))
    )
    (net (code "57") (name "unconnected-(U2-PadDCD#)") (class "Default")
      (node (ref "U2") (pin "DCD#") (pinfunction "DCD#_DCD#") (pintype "bidirectional"))
    )
    (net (code "58") (name "unconnected-(U2-PadDSR#)") (class "Default")
      (node (ref "U2") (pin "DSR#") (pinfunction "DSR#_DSR#") (pintype "bidirectional"))
    )
    (net (code "59") (name "unconnected-(U2-PadRI#)") (class "Default")
      (node (ref "U2") (pin "RI#") (pinfunction "RI#_RI#") (pintype "bidirectional"))
    )
    (net (code "60") (name "unconnected-(U2-PadRTS#)") (class "Default")
      (node (ref "U2") (pin "RTS#") (pinfunction "RTS#_RTS#") (pintype "bidirectional"))
    )
    (net (code "61") (name "unconnected-(U5-AREF-Pad20)") (class "Default")
      (node (ref "U5") (pin "20") (pinfunction "AREF_20") (pintype "input"))
    )
    (net (code "62") (name "unconnected-(U7-NC-Pad6)") (class "Default")
      (node (ref "U7") (pin "6") (pinfunction "NC_6") (pintype "bidirectional"))
    )
    (net (code "63") (name "unconnected-(U7-NC-Pad8)") (class "Default")
      (node (ref "U7") (pin "8") (pinfunction "NC_8") (pintype "bidirectional"))
    )
    (net (code "64") (name "unconnected-(U7-RESET-Pad5)") (class "Default")
      (node (ref "U7") (pin "5") (pinfunction "RESET_5") (pintype "bidirectional"))
    )
    (net (code "65") (name "unconnected-(U9-CSB-Pad2)") (class "Default")
      (node (ref "U9") (pin "2") (pinfunction "CSB_2") (pintype "input"))
    )
    (net (code "66") (name "unconnected-(U10-INT-Pad2)") (class "Default")
      (node (ref "U10") (pin "2") (pinfunction "INT_2") (pintype "output"))
    )
    (net (code "67") (name "unconnected-(U10-NC-Pad4)") (class "Default")
      (node (ref "U10") (pin "4") (pinfunction "NC_4") (pintype "no_connect"))
    )
    (net (code "68") (name "unconnected-(U11-DIO1-Pad15)") (class "Default")
      (node (ref "U11") (pin "15") (pinfunction "DIO1_15") (pintype "bidirectional"))
    )
    (net (code "69") (name "unconnected-(U11-DIO2-Pad16)") (class "Default")
      (node (ref "U11") (pin "16") (pinfunction "DIO2_16") (pintype "bidirectional"))
    )
    (net (code "70") (name "unconnected-(U11-DIO3-Pad11)") (class "Default")
      (node (ref "U11") (pin "11") (pinfunction "DIO3_11") (pintype "bidirectional"))
    )
    (net (code "71") (name "unconnected-(U11-DIO4-Pad12)") (class "Default")
      (node (ref "U11") (pin "12") (pinfunction "DIO4_12") (pintype "bidirectional"))
    )
    (net (code "72") (name "unconnected-(U11-DIO5-Pad7)") (class "Default")
      (node (ref "U11") (pin "7") (pinfunction "DIO5_7") (pintype "bidirectional"))
    )
    (net (code "73") (name "unconnected-(U11-RESET-Pad6)") (class "Default")
      (node (ref "U11") (pin "6") (pinfunction "RESET_6") (pintype "input"))
    )
    (net (code "74") (name "unconnected-(U12-PadAOT)") (class "Default")
      (node (ref "U12") (pin "AOT") (pinfunction "AOT_AOT") (pintype "bidirectional"))
    )
    (net (code "75") (name "unconnected-(U12-PadHD)") (class "Default")
      (node (ref "U12") (pin "HD") (pinfunction "HD_HD") (pintype "bidirectional"))
    )
    (net (code "76") (name "unconnected-(U12-PadPWM)") (class "Default")
      (node (ref "U12") (pin "PWM") (pinfunction "PWM_PWM") (pintype "bidirectional"))
    )
    (net (code "77") (name "unconnected-(U12-PadSR)") (class "Default")
      (node (ref "U12") (pin "SR") (pinfunction "SR_SR") (pintype "bidirectional"))
    )
    (net (code "78") (name "unconnected-(U12-PadVOUT)") (class "Default")
      (node (ref "U12") (pin "VOUT") (pinfunction "VOUT_VOUT") (pintype "bidirectional"))
    )
    (net (code "79") (name "unconnected-(U13-AUX-Pad8)") (class "Default")
      (node (ref "U13") (pin "8") (pinfunction "AUX_8") (pintype "bidirectional"))
    )
    (net (code "80") (name "unconnected-(U13-INT-Pad3)") (class "Default")
      (node (ref "U13") (pin "3") (pinfunction "INT_3") (pintype "bidirectional"))
    )
    (net (code "81") (name "unconnected-(U13-PWM-Pad4)") (class "Default")
      (node (ref "U13") (pin "4") (pinfunction "PWM_4") (pintype "bidirectional"))
    )
    (net (code "82") (name "unconnected-(U13-RESET-Pad2)") (class "Default")
      (node (ref "U13") (pin "2") (pinfunction "RESET_2") (pintype "bidirectional"))
    )
    (net (code "83") (name "unconnected-(U13-SENSE-Pad5)") (class "Default")
      (node (ref "U13") (pin "5") (pinfunction "SENSE_5") (pintype "bidirectional"))
    )
  )
)
